# Prometheus.net
KiCad netlist of a schematic drawn in Altium Designer
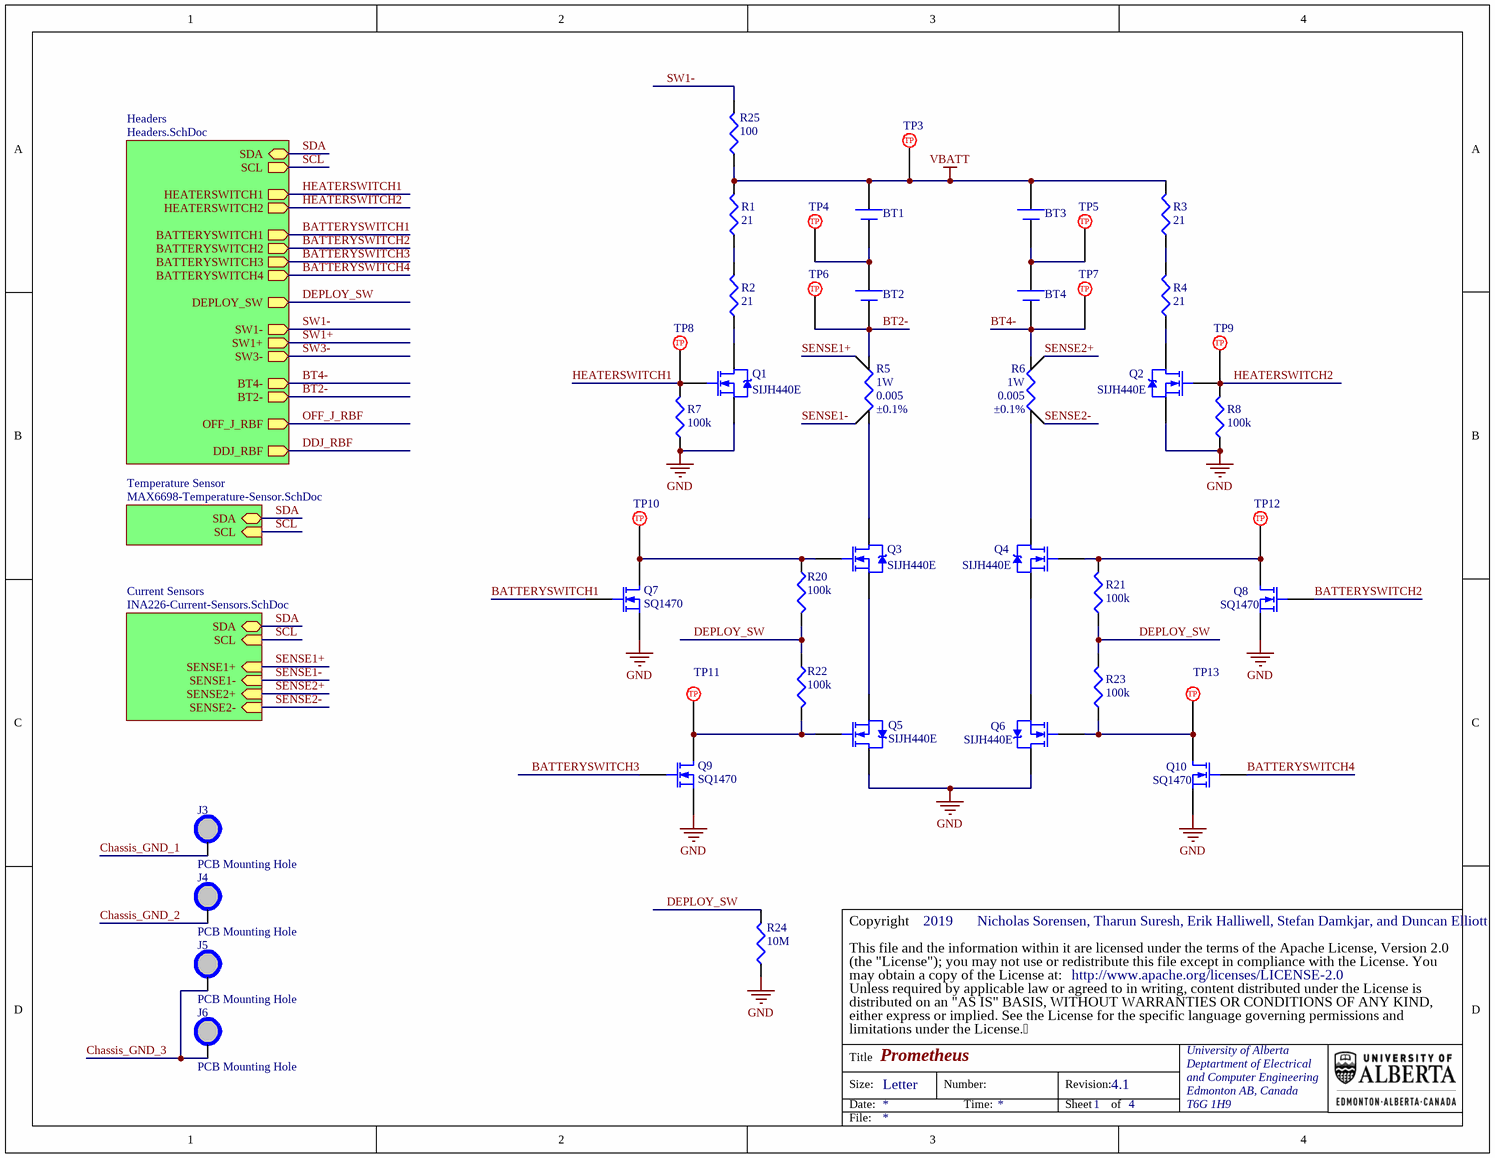
[diagram p0: Prometheus.SchDoc]

(export (version "E")
  (design (tool "Eeschema 10.0.6"))
  (components
    (comp (ref "BT1")
      (value "NCR18650PF")
      (footprint "ORB-PROTECTED18650")
      (description "18650 Battery-Panasonic Protected 2900mAh NCR18650PF Li-ion inside-10 Amp Dual Protection")
      (fields
        (field (name "PART NUMBER") "PBT-ORB-00001")
        (field (name "MANUFACTURER PART NUMBER") "BRB-2900")
        (field (name "PUBLISHER") "AlbertaSat")
      )
      (libsource (lib "Database") (part "Single-cell Battery"))
    )
    (comp (ref "BT2")
      (value "NCR18650PF")
      (footprint "ORB-PROTECTED18650")
      (description "18650 Battery-Panasonic Protected 2900mAh NCR18650PF Li-ion inside-10 Amp Dual Protection")
      (fields
        (field (name "PART NUMBER") "PBT-ORB-00001")
        (field (name "MANUFACTURER PART NUMBER") "BRB-2900")
        (field (name "PUBLISHER") "AlbertaSat")
      )
      (libsource (lib "Database") (part "Single-cell Battery"))
    )
    (comp (ref "BT3")
      (value "NCR18650PF")
      (footprint "ORB-PROTECTED18650")
      (description "18650 Battery-Panasonic Protected 2900mAh NCR18650PF Li-ion inside-10 Amp Dual Protection")
      (fields
        (field (name "PART NUMBER") "PBT-ORB-00001")
        (field (name "MANUFACTURER PART NUMBER") "BRB-2900")
        (field (name "PUBLISHER") "AlbertaSat")
      )
      (libsource (lib "Database") (part "Single-cell Battery"))
    )
    (comp (ref "BT4")
      (value "NCR18650PF")
      (footprint "ORB-PROTECTED18650")
      (description "18650 Battery-Panasonic Protected 2900mAh NCR18650PF Li-ion inside-10 Amp Dual Protection")
      (fields
        (field (name "PART NUMBER") "PBT-ORB-00001")
        (field (name "MANUFACTURER PART NUMBER") "BRB-2900")
        (field (name "PUBLISHER") "AlbertaSat")
      )
      (libsource (lib "Database") (part "Single-cell Battery"))
    )
    (comp (ref "J3")
      (value "PCB Mounting Hole")
      (footprint "Custom-prometheus:PCB Mounting Hole")
      (libsource (lib "Custom-Prometheus") (part "PCB Mounting Hole"))
    )
    (comp (ref "J4")
      (value "PCB Mounting Hole")
      (footprint "Custom-prometheus:PCB Mounting Hole")
      (libsource (lib "Custom-Prometheus") (part "PCB Mounting Hole"))
    )
    (comp (ref "J5")
      (value "PCB Mounting Hole")
      (footprint "Custom-prometheus:PCB Mounting Hole")
      (libsource (lib "Custom-Prometheus") (part "PCB Mounting Hole"))
    )
    (comp (ref "J6")
      (value "PCB Mounting Hole")
      (footprint "Custom-prometheus:PCB Mounting Hole")
      (libsource (lib "Custom-Prometheus") (part "PCB Mounting Hole"))
    )
    (comp (ref "Q1")
      (value "SIJH440E")
      (footprint "VSH-POWERPAK8X8L")
      (description "NMOS-2")
      (fields
        (field (name "PART NUMBER") "PQ-VSH-00270")
        (field (name "MANUFACTURER PART NUMBER") "SIJH440E-T1-GE3")
        (field (name "PUBLISHER") "AlbertaSat")
      )
      (libsource (lib "Database") (part "NMOS-2"))
    )
    (comp (ref "Q2")
      (value "SIJH440E")
      (footprint "VSH-POWERPAK8X8L")
      (description "NMOS-2")
      (fields
        (field (name "PART NUMBER") "PQ-VSH-00270")
        (field (name "MANUFACTURER PART NUMBER") "SIJH440E-T1-GE3")
        (field (name "PUBLISHER") "AlbertaSat")
      )
      (libsource (lib "Database") (part "NMOS-2"))
    )
    (comp (ref "Q3")
      (value "SIJH440E")
      (footprint "VSH-POWERPAK8X8L")
      (description "NMOS-2")
      (fields
        (field (name "PART NUMBER") "PQ-VSH-00270")
        (field (name "MANUFACTURER PART NUMBER") "SIJH440E-T1-GE3")
        (field (name "PUBLISHER") "AlbertaSat")
      )
      (libsource (lib "Database") (part "NMOS-2"))
    )
    (comp (ref "Q4")
      (value "SIJH440E")
      (footprint "VSH-POWERPAK8X8L")
      (description "NMOS-2")
      (fields
        (field (name "PART NUMBER") "PQ-VSH-00270")
        (field (name "MANUFACTURER PART NUMBER") "SIJH440E-T1-GE3")
        (field (name "PUBLISHER") "AlbertaSat")
      )
      (libsource (lib "Database") (part "NMOS-2"))
    )
    (comp (ref "Q5")
      (value "SIJH440E")
      (footprint "VSH-POWERPAK8X8L")
      (description "NMOS-2")
      (fields
        (field (name "PART NUMBER") "PQ-VSH-00270")
        (field (name "MANUFACTURER PART NUMBER") "SIJH440E-T1-GE3")
        (field (name "PUBLISHER") "AlbertaSat")
      )
      (libsource (lib "Database") (part "NMOS-2"))
    )
    (comp (ref "Q6")
      (value "SIJH440E")
      (footprint "VSH-POWERPAK8X8L")
      (description "NMOS-2")
      (fields
        (field (name "PART NUMBER") "PQ-VSH-00270")
        (field (name "MANUFACTURER PART NUMBER") "SIJH440E-T1-GE3")
        (field (name "PUBLISHER") "AlbertaSat")
      )
      (libsource (lib "Database") (part "NMOS-2"))
    )
    (comp (ref "Q7")
      (value "SQ1470")
      (footprint "VSH-SQ1470AEH")
      (description "MOSFET N-CH 30V 2.8A SC70")
      (fields
        (field (name "PART NUMBER") "PQ-VSH-00227")
        (field (name "MANUFACTURER PART NUMBER") "SQ1470AEH-T1_GE3")
        (field (name "PUBLISHER") "AlbertaSat")
      )
      (libsource (lib "Database") (part "MOSFET-N"))
    )
    (comp (ref "Q8")
      (value "SQ1470")
      (footprint "VSH-SQ1470AEH")
      (description "MOSFET N-CH 30V 2.8A SC70")
      (fields
        (field (name "PART NUMBER") "PQ-VSH-00227")
        (field (name "MANUFACTURER PART NUMBER") "SQ1470AEH-T1_GE3")
        (field (name "PUBLISHER") "AlbertaSat")
      )
      (libsource (lib "Database") (part "MOSFET-N"))
    )
    (comp (ref "Q9")
      (value "SQ1470")
      (footprint "VSH-SQ1470AEH")
      (description "MOSFET N-CH 30V 2.8A SC70")
      (fields
        (field (name "PART NUMBER") "PQ-VSH-00227")
        (field (name "MANUFACTURER PART NUMBER") "SQ1470AEH-T1_GE3")
        (field (name "PUBLISHER") "AlbertaSat")
      )
      (libsource (lib "Database") (part "MOSFET-N"))
    )
    (comp (ref "Q10")
      (value "SQ1470")
      (footprint "VSH-SQ1470AEH")
      (description "MOSFET N-CH 30V 2.8A SC70")
      (fields
        (field (name "PART NUMBER") "PQ-VSH-00227")
        (field (name "MANUFACTURER PART NUMBER") "SQ1470AEH-T1_GE3")
        (field (name "PUBLISHER") "AlbertaSat")
      )
      (libsource (lib "Database") (part "MOSFET-N"))
    )
    (comp (ref "R1")
      (value "21")
      (footprint "VSH-CPF1")
      (description "21 Ohms ±1% 1W Through Hole Resistor Axial Flame Proof, Moisture Resistant, Safety Metal Film")
      (fields
        (field (name "PART NUMBER") "PR-VSH-00269")
        (field (name "MANUFACTURER PART NUMBER") "CPF121R000FKEE6")
        (field (name "PUBLISHER") "AlbertaSat")
      )
      (libsource (lib "Database") (part "Res3"))
    )
    (comp (ref "R2")
      (value "21")
      (footprint "VSH-CPF1")
      (description "21 Ohms ±1% 1W Through Hole Resistor Axial Flame Proof, Moisture Resistant, Safety Metal Film")
      (fields
        (field (name "PART NUMBER") "PR-VSH-00269")
        (field (name "MANUFACTURER PART NUMBER") "CPF121R000FKEE6")
        (field (name "PUBLISHER") "AlbertaSat")
      )
      (libsource (lib "Database") (part "Res3"))
    )
    (comp (ref "R3")
      (value "21")
      (footprint "VSH-CPF1")
      (description "21 Ohms ±1% 1W Through Hole Resistor Axial Flame Proof, Moisture Resistant, Safety Metal Film")
      (fields
        (field (name "PART NUMBER") "PR-VSH-00269")
        (field (name "MANUFACTURER PART NUMBER") "CPF121R000FKEE6")
        (field (name "PUBLISHER") "AlbertaSat")
      )
      (libsource (lib "Database") (part "Res3"))
    )
    (comp (ref "R4")
      (value "21")
      (footprint "VSH-CPF1")
      (description "21 Ohms ±1% 1W Through Hole Resistor Axial Flame Proof, Moisture Resistant, Safety Metal Film")
      (fields
        (field (name "PART NUMBER") "PR-VSH-00269")
        (field (name "MANUFACTURER PART NUMBER") "CPF121R000FKEE6")
        (field (name "PUBLISHER") "AlbertaSat")
      )
      (libsource (lib "Database") (part "Res3"))
    )
    (comp (ref "R5")
      (value "0.005")
      (footprint "VSH-2512R4B")
      (description "RES SMD 0.005 OHM 0.1% 1W 2512")
      (fields
        (field (name "POWER - RATED") "1W")
        (field (name "TOLERANCE") "±0.1%")
        (field (name "PART NUMBER") "PR-VSH-00234")
        (field (name "MANUFACTURER PART NUMBER") "Y14870R00500B9R")
        (field (name "PUBLISHER") "AlbertaSat")
      )
      (libsource (lib "Database") (part "Res Sense"))
    )
    (comp (ref "R6")
      (value "0.005")
      (footprint "VSH-2512R4B")
      (description "RES SMD 0.005 OHM 0.1% 1W 2512")
      (fields
        (field (name "POWER - RATED") "1W")
        (field (name "TOLERANCE") "±0.1%")
        (field (name "PART NUMBER") "PR-VSH-00234")
        (field (name "MANUFACTURER PART NUMBER") "Y14870R00500B9R")
        (field (name "PUBLISHER") "AlbertaSat")
      )
      (libsource (lib "Database") (part "Res Sense"))
    )
    (comp (ref "R7")
      (value "100k")
      (footprint "PANA-ERJ6EN")
      (description "RES SMD 100K OHM 1% 1/8W 0805")
      (fields
        (field (name "PART NUMBER") "18749")
        (field (name "MANUFACTURER PART NUMBER") "ERJ-6ENF1003V")
        (field (name "PUBLISHER") "Altium Limited")
      )
      (libsource (lib "Database") (part "Res3"))
    )
    (comp (ref "R8")
      (value "100k")
      (footprint "PANA-ERJ6EN")
      (description "RES SMD 100K OHM 1% 1/8W 0805")
      (fields
        (field (name "PART NUMBER") "18749")
        (field (name "MANUFACTURER PART NUMBER") "ERJ-6ENF1003V")
        (field (name "PUBLISHER") "Altium Limited")
      )
      (libsource (lib "Database") (part "Res3"))
    )
    (comp (ref "R20")
      (value "100k")
      (footprint "PANA-ERJ6EN")
      (description "RES SMD 100K OHM 1% 1/8W 0805")
      (fields
        (field (name "PART NUMBER") "18749")
        (field (name "MANUFACTURER PART NUMBER") "ERJ-6ENF1003V")
        (field (name "PUBLISHER") "Altium Limited")
      )
      (libsource (lib "Database") (part "Res3"))
    )
    (comp (ref "R21")
      (value "100k")
      (footprint "PANA-ERJ6EN")
      (description "RES SMD 100K OHM 1% 1/8W 0805")
      (fields
        (field (name "PART NUMBER") "18749")
        (field (name "MANUFACTURER PART NUMBER") "ERJ-6ENF1003V")
        (field (name "PUBLISHER") "Altium Limited")
      )
      (libsource (lib "Database") (part "Res3"))
    )
    (comp (ref "R22")
      (value "100k")
      (footprint "PANA-ERJ6EN")
      (description "RES SMD 100K OHM 1% 1/8W 0805")
      (fields
        (field (name "PART NUMBER") "18749")
        (field (name "MANUFACTURER PART NUMBER") "ERJ-6ENF1003V")
        (field (name "PUBLISHER") "Altium Limited")
      )
      (libsource (lib "Database") (part "Res3"))
    )
    (comp (ref "R23")
      (value "100k")
      (footprint "PANA-ERJ6EN")
      (description "RES SMD 100K OHM 1% 1/8W 0805")
      (fields
        (field (name "PART NUMBER") "18749")
        (field (name "MANUFACTURER PART NUMBER") "ERJ-6ENF1003V")
        (field (name "PUBLISHER") "Altium Limited")
      )
      (libsource (lib "Database") (part "Res3"))
    )
    (comp (ref "R24")
      (value "10M")
      (footprint "VSH-0603MCT")
      (description "RES SMD 10M OHM 1% 1/8W 0603")
      (fields
        (field (name "PART NUMBER") "PR-VSH-00224")
        (field (name "MANUFACTURER PART NUMBER") "MCT06030C1005FP500")
        (field (name "PUBLISHER") "AlbertaSat")
      )
      (libsource (lib "Database") (part "Res3"))
    )
    (comp (ref "R25")
      (value "100")
      (footprint "VSH-0805MCU")
      (description "RES SMD 100 OHM 1% 1/5W 0805")
      (fields
        (field (name "PART NUMBER") "PR-VSH-00029")
        (field (name "MANUFACTURER PART NUMBER") "MCU08050C1000FP500")
        (field (name "PUBLISHER") "AlbertaSat")
      )
      (libsource (lib "Database") (part "Res3"))
    )
    (comp (ref "TP3")
      (value "5017")
      (footprint "KS-5017")
      (description "PC TEST POINT MINI SMD")
      (fields (field (name "PART NUMBER") "PTP-KS-00001") (field (name "PUBLISHER") "AlbertaSat"))
      (libsource (lib "Database") (part "5017"))
    )
    (comp (ref "TP4")
      (value "5017")
      (footprint "KS-5017")
      (description "PC TEST POINT MINI SMD")
      (fields (field (name "PART NUMBER") "PTP-KS-00001") (field (name "PUBLISHER") "AlbertaSat"))
      (libsource (lib "Database") (part "5017"))
    )
    (comp (ref "TP5")
      (value "5017")
      (footprint "KS-5017")
      (description "PC TEST POINT MINI SMD")
      (fields (field (name "PART NUMBER") "PTP-KS-00001") (field (name "PUBLISHER") "AlbertaSat"))
      (libsource (lib "Database") (part "5017"))
    )
    (comp (ref "TP6")
      (value "5017")
      (footprint "KS-5017")
      (description "PC TEST POINT MINI SMD")
      (fields (field (name "PART NUMBER") "PTP-KS-00001") (field (name "PUBLISHER") "AlbertaSat"))
      (libsource (lib "Database") (part "5017"))
    )
    (comp (ref "TP7")
      (value "5017")
      (footprint "KS-5017")
      (description "PC TEST POINT MINI SMD")
      (fields (field (name "PART NUMBER") "PTP-KS-00001") (field (name "PUBLISHER") "AlbertaSat"))
      (libsource (lib "Database") (part "5017"))
    )
    (comp (ref "TP8")
      (value "5017")
      (footprint "KS-5017")
      (description "PC TEST POINT MINI SMD")
      (fields (field (name "PART NUMBER") "PTP-KS-00001") (field (name "PUBLISHER") "AlbertaSat"))
      (libsource (lib "Database") (part "5017"))
    )
    (comp (ref "TP9")
      (value "5017")
      (footprint "KS-5017")
      (description "PC TEST POINT MINI SMD")
      (fields (field (name "PART NUMBER") "PTP-KS-00001") (field (name "PUBLISHER") "AlbertaSat"))
      (libsource (lib "Database") (part "5017"))
    )
    (comp (ref "TP10")
      (value "5017")
      (footprint "KS-5017")
      (description "3")
      (fields (field (name "PART NUMBER") "PTP-KS-00001") (field (name "PUBLISHER") "AlbertaSat"))
      (libsource (lib "Database") (part "5017"))
    )
    (comp (ref "TP11")
      (value "5017")
      (footprint "KS-5017")
      (description "PC TEST POINT MINI SMD")
      (fields (field (name "PART NUMBER") "PTP-KS-00001") (field (name "PUBLISHER") "AlbertaSat"))
      (libsource (lib "Database") (part "5017"))
    )
    (comp (ref "TP12")
      (value "5017")
      (footprint "KS-5017")
      (description "PC TEST POINT MINI SMD")
      (fields (field (name "PART NUMBER") "PTP-KS-00001") (field (name "PUBLISHER") "AlbertaSat"))
      (libsource (lib "Database") (part "5017"))
    )
    (comp (ref "TP13")
      (value "5017")
      (footprint "KS-5017")
      (description "PC TEST POINT MINI SMD")
      (fields (field (name "PART NUMBER") "PTP-KS-00001") (field (name "PUBLISHER") "AlbertaSat"))
      (libsource (lib "Database") (part "5017"))
    )
  )
  (nets
    (net (code "1") (name "/BATTERYSWITCH1") (class "Default")
      (node (ref "Q7") (pin "2") (pinfunction "2_2") (pintype "passive"))
    )
    (net (code "2") (name "/BATTERYSWITCH2") (class "Default")
      (node (ref "Q8") (pin "2") (pinfunction "2_2") (pintype "passive"))
    )
    (net (code "3") (name "/BATTERYSWITCH3") (class "Default")
      (node (ref "Q9") (pin "2") (pinfunction "2_2") (pintype "passive"))
    )
    (net (code "4") (name "/BATTERYSWITCH4") (class "Default")
      (node (ref "Q10") (pin "2") (pinfunction "2_2") (pintype "passive"))
    )
    (net (code "5") (name "/BT2-") (class "Default")
      (node (ref "BT2") (pin "2") (pinfunction "-_2") (pintype "passive"))
      (node (ref "R5") (pin "2") (pinfunction "I2_2") (pintype "passive"))
      (node (ref "TP6") (pin "1") (pinfunction "1_1") (pintype "passive"))
    )
    (net (code "6") (name "/BT4-") (class "Default")
      (node (ref "BT4") (pin "2") (pinfunction "-_2") (pintype "passive"))
      (node (ref "R6") (pin "1") (pinfunction "I1_1") (pintype "passive"))
      (node (ref "TP7") (pin "1") (pinfunction "1_1") (pintype "passive"))
    )
    (net (code "7") (name "/Chassis_GND_1") (class "Default")
      (node (ref "J3") (pin "1") (pinfunction "0_1") (pintype "passive"))
    )
    (net (code "8") (name "/Chassis_GND_2") (class "Default")
      (node (ref "J4") (pin "1") (pinfunction "0_1") (pintype "passive"))
    )
    (net (code "9") (name "/Chassis_GND_3") (class "Default")
      (node (ref "J5") (pin "1") (pinfunction "0_1") (pintype "passive"))
      (node (ref "J6") (pin "1") (pinfunction "0_1") (pintype "passive"))
    )
    (net (code "11") (name "/DEPLOY_SW") (class "Default")
      (node (ref "R20") (pin "2") (pinfunction "2_2") (pintype "passive"))
      (node (ref "R21") (pin "1") (pinfunction "1_1") (pintype "passive"))
      (node (ref "R22") (pin "1") (pinfunction "1_1") (pintype "passive"))
      (node (ref "R23") (pin "2") (pinfunction "2_2") (pintype "passive"))
      (node (ref "R24") (pin "2") (pinfunction "2_2") (pintype "passive"))
    )
    (net (code "12") (name "/HEATERSWITCH1") (class "Default")
      (node (ref "Q1") (pin "1") (pinfunction "G_1") (pintype "passive"))
      (node (ref "R7") (pin "2") (pinfunction "2_2") (pintype "passive"))
      (node (ref "TP8") (pin "1") (pinfunction "1_1") (pintype "passive"))
    )
    (net (code "13") (name "/HEATERSWITCH2") (class "Default")
      (node (ref "Q2") (pin "1") (pinfunction "G_1") (pintype "passive"))
      (node (ref "R8") (pin "2") (pinfunction "2_2") (pintype "passive"))
      (node (ref "TP9") (pin "1") (pinfunction "1_1") (pintype "passive"))
    )
    (net (code "17") (name "/SENSE1+") (class "Default")
      (node (ref "R5") (pin "3") (pinfunction "S2_3") (pintype "passive"))
    )
    (net (code "18") (name "/SENSE1-") (class "Default")
      (node (ref "R5") (pin "4") (pinfunction "S1_4") (pintype "passive"))
    )
    (net (code "19") (name "/SENSE2+") (class "Default")
      (node (ref "R6") (pin "4") (pinfunction "S1_4") (pintype "passive"))
    )
    (net (code "20") (name "/SENSE2-") (class "Default")
      (node (ref "R6") (pin "3") (pinfunction "S2_3") (pintype "passive"))
    )
    (net (code "22") (name "/SW1-") (class "Default")
      (node (ref "R25") (pin "2") (pinfunction "2_2") (pintype "passive"))
    )
    (net (code "24") (name "GND") (class "Default")
      (node (ref "Q1") (pin "3") (pinfunction "S_3") (pintype "passive"))
      (node (ref "Q10") (pin "3") (pinfunction "3_3") (pintype "passive"))
      (node (ref "Q2") (pin "3") (pinfunction "S_3") (pintype "passive"))
      (node (ref "Q5") (pin "2") (pinfunction "D_2") (pintype "passive"))
      (node (ref "Q6") (pin "2") (pinfunction "D_2") (pintype "passive"))
      (node (ref "Q7") (pin "3") (pinfunction "3_3") (pintype "passive"))
      (node (ref "Q8") (pin "3") (pinfunction "3_3") (pintype "passive"))
      (node (ref "Q9") (pin "3") (pinfunction "3_3") (pintype "passive"))
      (node (ref "R24") (pin "1") (pinfunction "1_1") (pintype "passive"))
      (node (ref "R7") (pin "1") (pinfunction "1_1") (pintype "passive"))
      (node (ref "R8") (pin "1") (pinfunction "1_1") (pintype "passive"))
    )
    (net (code "25") (name "Net-(BT1--)") (class "Default")
      (node (ref "BT1") (pin "2") (pinfunction "-_2") (pintype "passive"))
      (node (ref "BT2") (pin "1") (pinfunction "+_1") (pintype "passive"))
      (node (ref "TP4") (pin "1") (pinfunction "1_1") (pintype "passive"))
    )
    (net (code "26") (name "Net-(BT3--)") (class "Default")
      (node (ref "BT3") (pin "2") (pinfunction "-_2") (pintype "passive"))
      (node (ref "BT4") (pin "1") (pinfunction "+_1") (pintype "passive"))
      (node (ref "TP5") (pin "1") (pinfunction "1_1") (pintype "passive"))
    )
    (net (code "27") (name "Net-(Q1-D)") (class "Default")
      (node (ref "Q1") (pin "2") (pinfunction "D_2") (pintype "passive"))
      (node (ref "R2") (pin "1") (pinfunction "1_1") (pintype "passive"))
    )
    (net (code "28") (name "Net-(Q2-D)") (class "Default")
      (node (ref "Q2") (pin "2") (pinfunction "D_2") (pintype "passive"))
      (node (ref "R4") (pin "1") (pinfunction "1_1") (pintype "passive"))
    )
    (net (code "29") (name "Net-(Q3-D)") (class "Default")
      (node (ref "Q3") (pin "2") (pinfunction "D_2") (pintype "passive"))
      (node (ref "R5") (pin "1") (pinfunction "I1_1") (pintype "passive"))
    )
    (net (code "30") (name "Net-(Q3-G)") (class "Default")
      (node (ref "Q3") (pin "1") (pinfunction "G_1") (pintype "passive"))
      (node (ref "Q7") (pin "1") (pinfunction "1_1") (pintype "passive"))
      (node (ref "R20") (pin "1") (pinfunction "1_1") (pintype "passive"))
      (node (ref "TP10") (pin "1") (pinfunction "1_1") (pintype "passive"))
    )
    (net (code "31") (name "Net-(Q3-S)") (class "Default")
      (node (ref "Q3") (pin "3") (pinfunction "S_3") (pintype "passive"))
      (node (ref "Q5") (pin "3") (pinfunction "S_3") (pintype "passive"))
    )
    (net (code "32") (name "Net-(Q4-D)") (class "Default")
      (node (ref "Q4") (pin "2") (pinfunction "D_2") (pintype "passive"))
      (node (ref "R6") (pin "2") (pinfunction "I2_2") (pintype "passive"))
    )
    (net (code "33") (name "Net-(Q4-G)") (class "Default")
      (node (ref "Q4") (pin "1") (pinfunction "G_1") (pintype "passive"))
      (node (ref "Q8") (pin "1") (pinfunction "1_1") (pintype "passive"))
      (node (ref "R21") (pin "2") (pinfunction "2_2") (pintype "passive"))
      (node (ref "TP12") (pin "1") (pinfunction "1_1") (pintype "passive"))
    )
    (net (code "34") (name "Net-(Q4-S)") (class "Default")
      (node (ref "Q4") (pin "3") (pinfunction "S_3") (pintype "passive"))
      (node (ref "Q6") (pin "3") (pinfunction "S_3") (pintype "passive"))
    )
    (net (code "35") (name "Net-(Q5-G)") (class "Default")
      (node (ref "Q5") (pin "1") (pinfunction "G_1") (pintype "passive"))
      (node (ref "Q9") (pin "1") (pinfunction "1_1") (pintype "passive"))
      (node (ref "R22") (pin "2") (pinfunction "2_2") (pintype "passive"))
      (node (ref "TP11") (pin "1") (pinfunction "1_1") (pintype "passive"))
    )
    (net (code "36") (name "Net-(Q6-G)") (class "Default")
      (node (ref "Q10") (pin "1") (pinfunction "1_1") (pintype "passive"))
      (node (ref "Q6") (pin "1") (pinfunction "G_1") (pintype "passive"))
      (node (ref "R23") (pin "1") (pinfunction "1_1") (pintype "passive"))
      (node (ref "TP13") (pin "1") (pinfunction "1_1") (pintype "passive"))
    )
    (net (code "37") (name "Net-(R1-Pad1)") (class "Default")
      (node (ref "R1") (pin "1") (pinfunction "1_1") (pintype "passive"))
      (node (ref "R2") (pin "2") (pinfunction "2_2") (pintype "passive"))
    )
    (net (code "38") (name "Net-(R3-Pad1)") (class "Default")
      (node (ref "R3") (pin "1") (pinfunction "1_1") (pintype "passive"))
      (node (ref "R4") (pin "2") (pinfunction "2_2") (pintype "passive"))
    )
    (net (code "39") (name "VBATT") (class "Default")
      (node (ref "BT1") (pin "1") (pinfunction "+_1") (pintype "passive"))
      (node (ref "BT3") (pin "1") (pinfunction "+_1") (pintype "passive"))
      (node (ref "R1") (pin "2") (pinfunction "2_2") (pintype "passive"))
      (node (ref "R25") (pin "1") (pinfunction "1_1") (pintype "passive"))
      (node (ref "R3") (pin "2") (pinfunction "2_2") (pintype "passive"))
      (node (ref "TP3") (pin "1") (pinfunction "1_1") (pintype "passive"))
    )
  )
)
